# RS485.net
KiCad netlist of a schematic drawn in Altium Designer
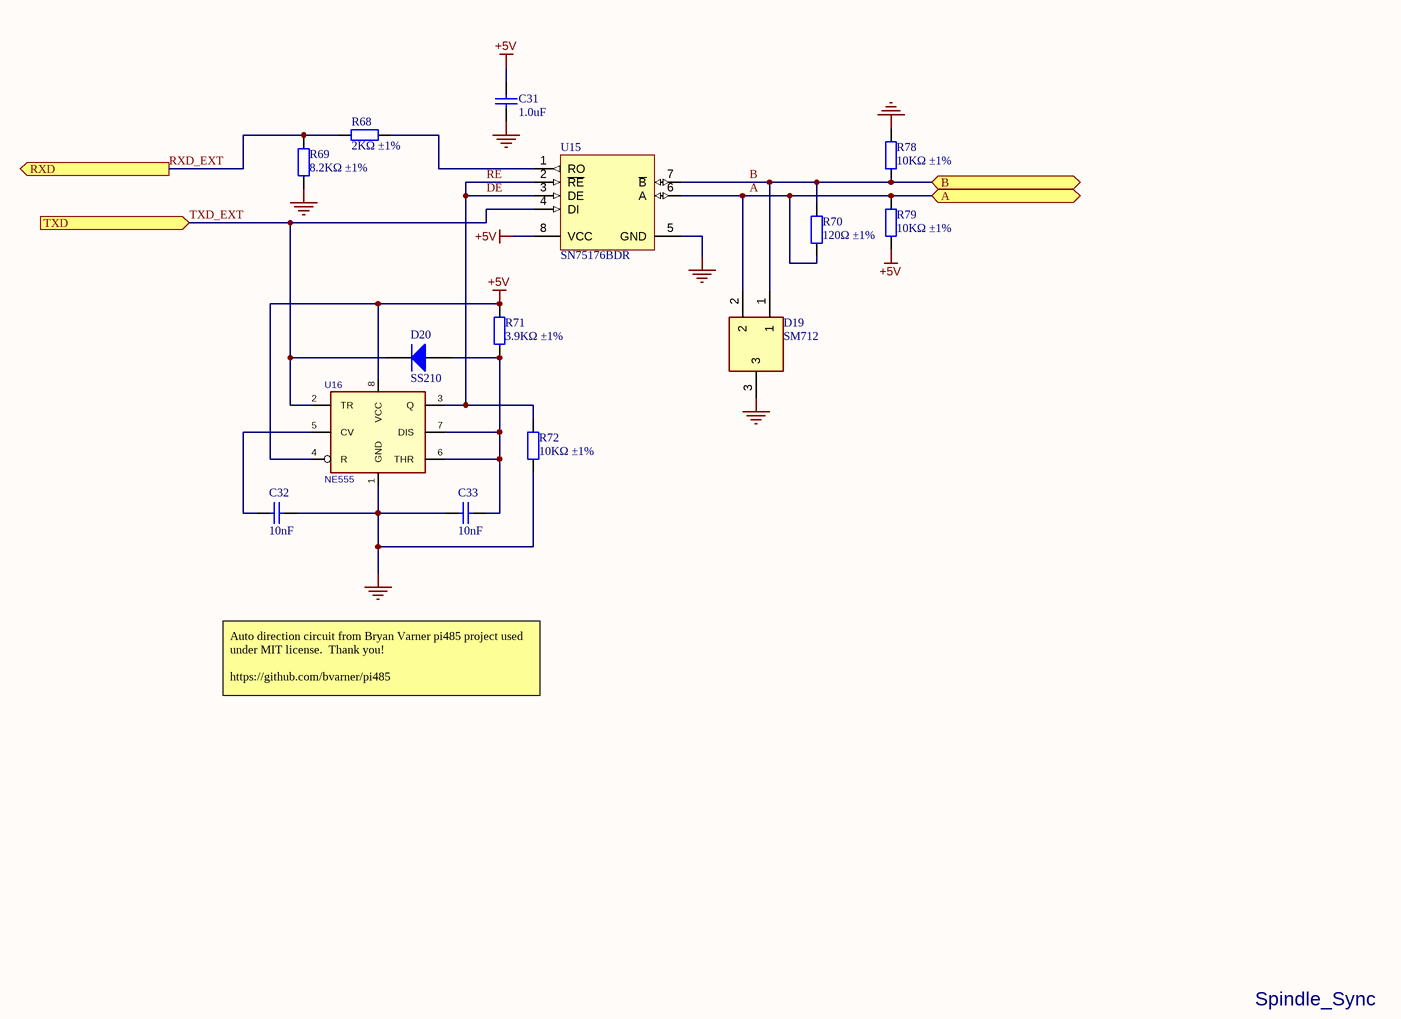
[diagram p0: RS485.SchDoc]

(export (version "E")
  (design (tool "Eeschema 10.0.6"))
  (components
    (comp (ref "C31")
      (value "1.0uF")
      (footprint "0402_C")
      (description "Chip capacitor")
      (fields
        (field (name "MANUFACTURER") "Samsung Electro-Mechanics")
        (field (name "PARTNUMBER") "CL05A105KA5NQNC")
      )
      (libsource (lib "Cap") (part "0402 1.0uF (105) 10% 25V"))
    )
    (comp (ref "C32")
      (value "10nF")
      (footprint "0402_C")
      (description "Chip capacitors")
      (fields
        (field (name "MANUFACTURER") "Samsung Electro-Mechanics")
        (field (name "PARTNUMBER") "CL05B103KB5NNNC")
      )
      (libsource (lib "Cap") (part "0402 10nF (103) 10% 50V"))
    )
    (comp (ref "C33")
      (value "10nF")
      (footprint "0402_C")
      (description "Chip capacitors")
      (fields
        (field (name "MANUFACTURER") "Samsung Electro-Mechanics")
        (field (name "PARTNUMBER") "CL05B103KB5NNNC")
      )
      (libsource (lib "Cap") (part "0402 10nF (103) 10% 50V"))
    )
    (comp (ref "D19")
      (value "SM712")
      (footprint "SamacSys:SOT95P230X117-3N")
      (description "Bidirectional 12V (Max), 7V (Max) 7.5V / 13.3V 10V / 20V 12A(8/20us) SOT-23-3 TVS RoHS")
      (libsource (lib "*") (part "CDSOT23-SM712"))
    )
    (comp (ref "D20")
      (value "SS210")
      (footprint "SMA(DO-214AC)_S1")
      (description "二极管")
      (libsource (lib "Diode") (part "SMA(DO-214AC) SS210"))
    )
    (comp (ref "R68")
      (value "2KΩ ±1%")
      (footprint "0402_R")
      (description "Chip resistor")
      (fields (field (name "MANUFACTURER") "Uniroyal Elec") (field (name "PARTNUMBER") "0402WGF2001TCE"))
      (libsource (lib "PrintNC_GRBLHAL_Breakout") (part "0402 2K (2001) 1%"))
    )
    (comp (ref "R69")
      (value "8.2KΩ ±1%")
      (footprint "0402_R")
      (description "Chip resistor")
      (fields (field (name "MANUFACTURER") "Uniroyal Elec") (field (name "PARTNUMBER") "0402WGF8201TCE"))
      (libsource (lib "PrintNC_GRBLHAL_Breakout") (part "0402 8.2K (8201) 1%"))
    )
    (comp (ref "R70")
      (value "120Ω ±1%")
      (footprint "0805_R")
      (description "Chip resistor")
      (fields (field (name "MANUFACTURER") "Uniroyal Elec") (field (name "POWER") "1/8W"))
      (libsource (lib "RES") (part "0805 120R (1200) 1%"))
    )
    (comp (ref "R71")
      (value "3.9KΩ ±1%")
      (footprint "0402_R")
      (description "Chip resistor")
      (fields (field (name "MANUFACTURER") "Uniroyal Elec") (field (name "PARTNUMBER") "0402WGF3901TCE"))
      (libsource (lib "PrintNC_GRBLHAL_Breakout") (part "0402 3.9K (3901) 1%"))
    )
    (comp (ref "R72")
      (value "10KΩ ±1%")
      (footprint "0402_R")
      (description "Chip resistor")
      (fields (field (name "MANUFACTURER") "Uniroyal Elec") (field (name "PARTNUMBER") "0402WGF1002TCE"))
      (libsource (lib "PrintNC_GRBLHAL_Breakout") (part "0402 10K (1002) 1%"))
    )
    (comp (ref "R78")
      (value "10KΩ ±1%")
      (footprint "0402_R")
      (description "Chip resistor")
      (fields (field (name "MANUFACTURER") "Uniroyal Elec") (field (name "PARTNUMBER") "0402WGF1002TCE"))
      (libsource (lib "PrintNC_GRBLHAL_Breakout") (part "0402 10K (1002) 1%"))
    )
    (comp (ref "R79")
      (value "10KΩ ±1%")
      (footprint "0402_R")
      (description "Chip resistor")
      (fields (field (name "MANUFACTURER") "Uniroyal Elec") (field (name "PARTNUMBER") "0402WGF1002TCE"))
      (libsource (lib "PrintNC_GRBLHAL_Breakout") (part "0402 10K (1002) 1%"))
    )
    (comp (ref "U15")
      (value "SN75176BDR")
      (footprint "SOIC-8_150mil")
      (description "RS-485/RS-422")
      (libsource (lib "PrintNC_GRBLHAL_Breakout") (part "SN75176BDR_[C7063]"))
    )
    (comp (ref "U16")
      (value "NE555")
      (footprint "SOIC-8_150mil")
      (fields (field (name "Comment") "NE555DR"))
      (libsource (lib "PrintNC_GRBLHAL_Breakout") (part "NE555"))
    )
  )
  (nets
    (net (code "1") (name "+5V") (class "Default")
      (node (ref "C31") (pin "2") (pinfunction "2_2") (pintype "passive"))
      (node (ref "R71") (pin "2") (pinfunction "2_2") (pintype "passive"))
      (node (ref "R79") (pin "1") (pinfunction "1_1") (pintype "passive"))
      (node (ref "U15") (pin "8") (pinfunction "VCC_8") (pintype "power_in"))
      (node (ref "U16") (pin "4") (pinfunction "R_4") (pintype "passive"))
      (node (ref "U16") (pin "8") (pinfunction "VCC_8") (pintype "passive"))
    )
    (net (code "2") (name "/A") (class "Default")
      (node (ref "D19") (pin "2") (pinfunction "2_2") (pintype "passive"))
      (node (ref "R70") (pin "1") (pinfunction "1_1") (pintype "passive"))
      (node (ref "R79") (pin "2") (pinfunction "2_2") (pintype "passive"))
      (node (ref "U15") (pin "6") (pinfunction "A_6") (pintype "bidirectional"))
    )
    (net (code "3") (name "/B") (class "Default")
      (node (ref "D19") (pin "1") (pinfunction "1_1") (pintype "passive"))
      (node (ref "R70") (pin "2") (pinfunction "2_2") (pintype "passive"))
      (node (ref "R78") (pin "1") (pinfunction "1_1") (pintype "passive"))
      (node (ref "U15") (pin "7") (pinfunction "~{B}_7") (pintype "bidirectional"))
    )
    (net (code "4") (name "/DE") (class "Default")
      (node (ref "R72") (pin "2") (pinfunction "2_2") (pintype "passive"))
      (node (ref "U15") (pin "2") (pinfunction "~{RE}_2") (pintype "input"))
      (node (ref "U15") (pin "3") (pinfunction "DE_3") (pintype "input"))
      (node (ref "U16") (pin "3") (pinfunction "Q_3") (pintype "passive"))
    )
    (net (code "5") (name "/RXD_EXT") (class "Default")
      (node (ref "R68") (pin "2") (pinfunction "2_2") (pintype "passive"))
      (node (ref "R69") (pin "1") (pinfunction "1_1") (pintype "passive"))
    )
    (net (code "6") (name "/TXD_EXT") (class "Default")
      (node (ref "D20") (pin "2") (pinfunction "K_2") (pintype "passive"))
      (node (ref "U15") (pin "4") (pinfunction "DI_4") (pintype "input"))
      (node (ref "U16") (pin "2") (pinfunction "TR_2") (pintype "passive"))
    )
    (net (code "7") (name "GND") (class "Default")
      (node (ref "C31") (pin "1") (pinfunction "1_1") (pintype "passive"))
      (node (ref "C32") (pin "2") (pinfunction "2_2") (pintype "passive"))
      (node (ref "C33") (pin "1") (pinfunction "1_1") (pintype "passive"))
      (node (ref "D19") (pin "3") (pinfunction "3_3") (pintype "passive"))
      (node (ref "R69") (pin "2") (pinfunction "2_2") (pintype "passive"))
      (node (ref "R72") (pin "1") (pinfunction "1_1") (pintype "passive"))
      (node (ref "R78") (pin "2") (pinfunction "2_2") (pintype "passive"))
      (node (ref "U15") (pin "5") (pinfunction "GND_5") (pintype "power_in"))
      (node (ref "U16") (pin "1") (pinfunction "GND_1") (pintype "passive"))
    )
    (net (code "8") (name "Net-(D20-A)") (class "Default")
      (node (ref "C33") (pin "2") (pinfunction "2_2") (pintype "passive"))
      (node (ref "D20") (pin "1") (pinfunction "A_1") (pintype "passive"))
      (node (ref "R71") (pin "1") (pinfunction "1_1") (pintype "passive"))
      (node (ref "U16") (pin "6") (pinfunction "THR_6") (pintype "passive"))
      (node (ref "U16") (pin "7") (pinfunction "DIS_7") (pintype "passive"))
    )
    (net (code "9") (name "Net-(U15-RO)") (class "Default")
      (node (ref "R68") (pin "1") (pinfunction "1_1") (pintype "passive"))
      (node (ref "U15") (pin "1") (pinfunction "RO_1") (pintype "output"))
    )
    (net (code "10") (name "Net-(U16-CV)") (class "Default")
      (node (ref "C32") (pin "1") (pinfunction "1_1") (pintype "passive"))
      (node (ref "U16") (pin "5") (pinfunction "CV_5") (pintype "passive"))
    )
  )
)
